# StepStick-Protector_v20.net
KiCad netlist of a schematic drawn in EAGLE
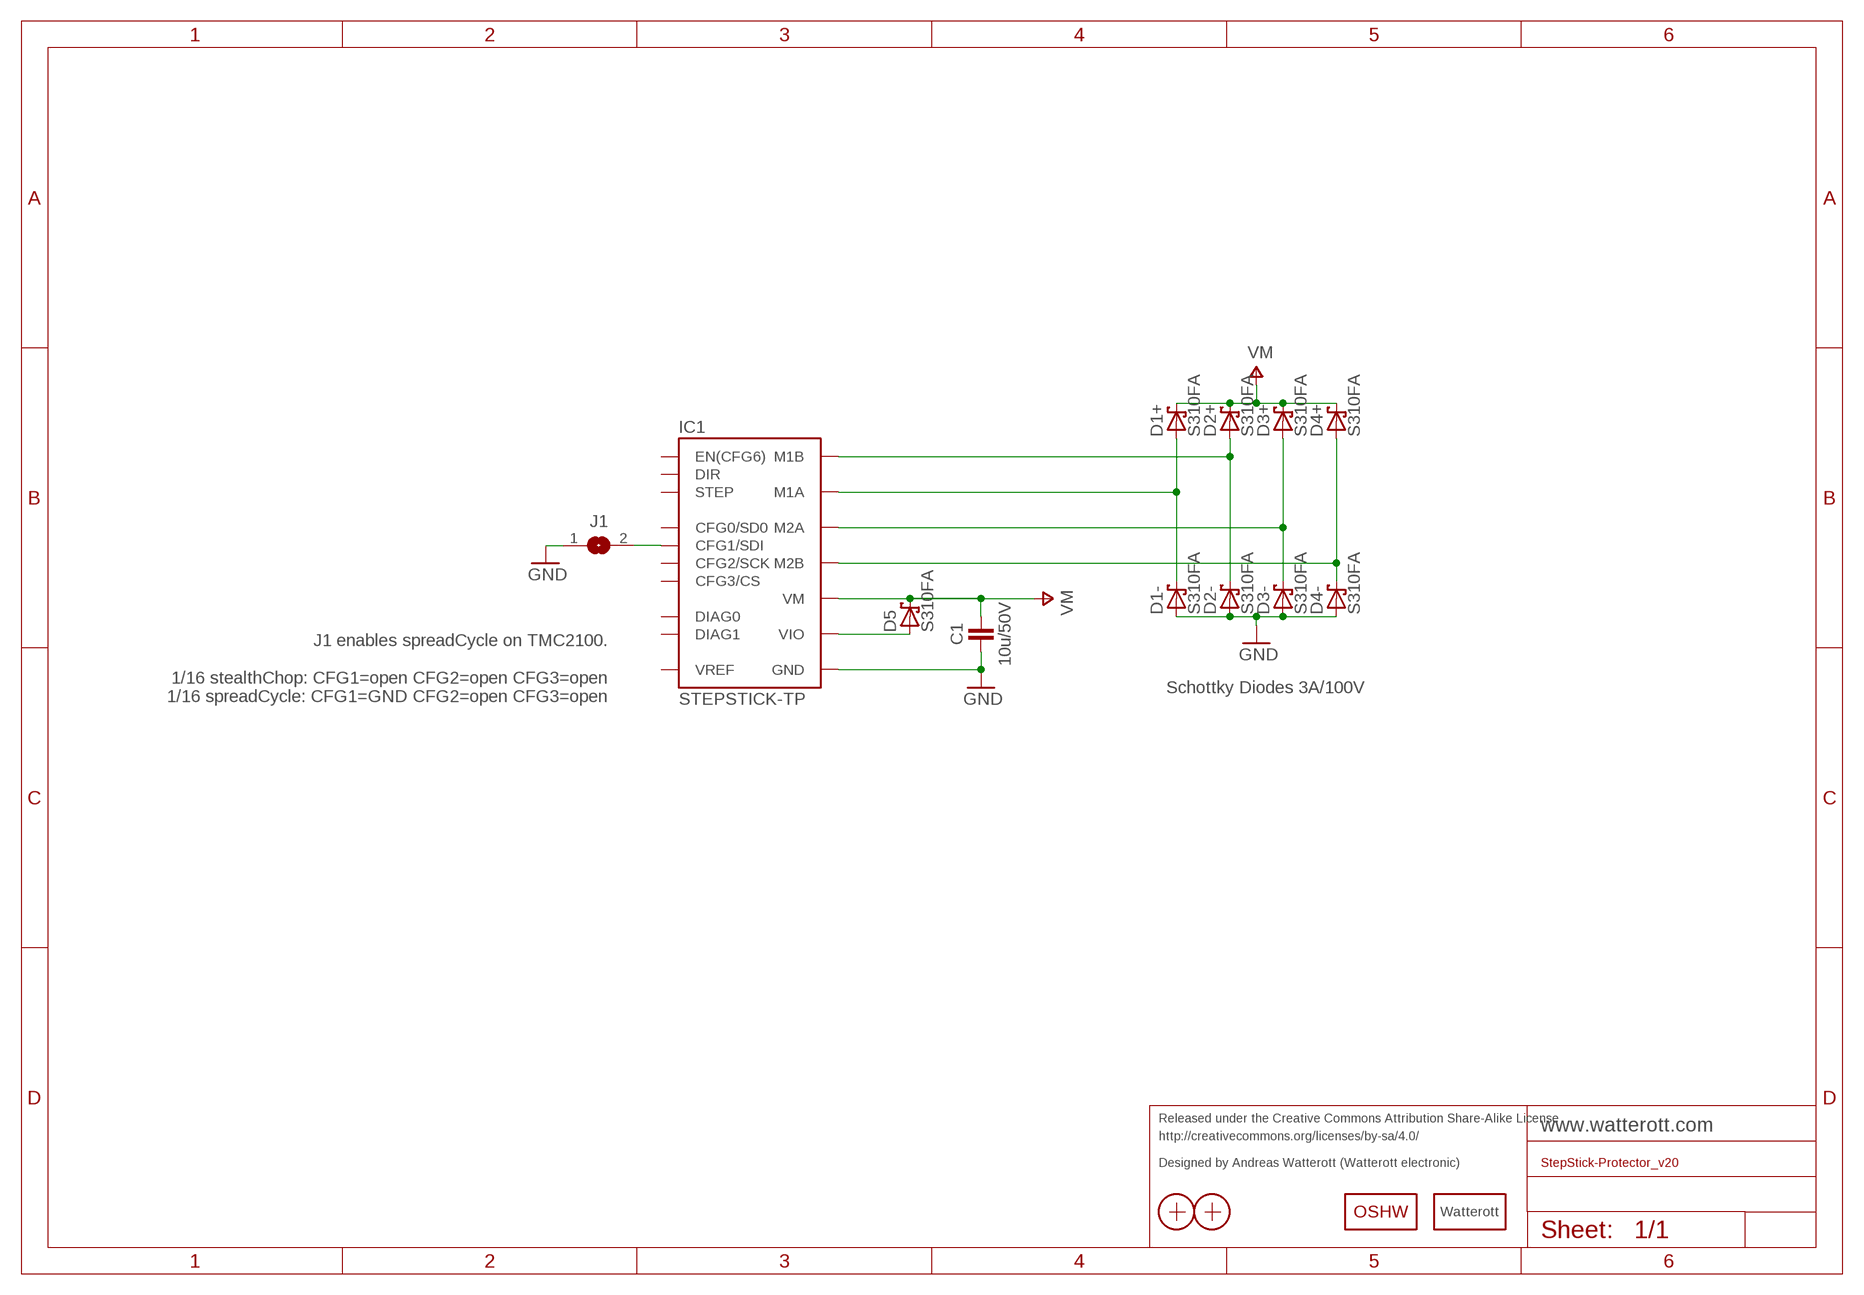
[diagram p0: schematic, sheet 1]

(export (version "E")
  (design (tool "Eeschema 10.0.6"))
  (components
    (comp (ref "C1")
      (value "10u/50V")
      (footprint "eagle-import:C1210")
      (libsource (lib "eagle-import") (part "CAPACITOR-1210"))
    )
    (comp (ref "D1+")
      (value "S310FA")
      (footprint "eagle-import:SOD123")
      (libsource (lib "eagle-import") (part "D_SCHOTTKY-SOD123"))
    )
    (comp (ref "D1-")
      (value "S310FA")
      (footprint "eagle-import:SOD123")
      (libsource (lib "eagle-import") (part "D_SCHOTTKY-SOD123"))
    )
    (comp (ref "D2+")
      (value "S310FA")
      (footprint "eagle-import:SOD123")
      (libsource (lib "eagle-import") (part "D_SCHOTTKY-SOD123"))
    )
    (comp (ref "D2-")
      (value "S310FA")
      (footprint "eagle-import:SOD123")
      (libsource (lib "eagle-import") (part "D_SCHOTTKY-SOD123"))
    )
    (comp (ref "D3+")
      (value "S310FA")
      (footprint "eagle-import:SOD123")
      (libsource (lib "eagle-import") (part "D_SCHOTTKY-SOD123"))
    )
    (comp (ref "D3-")
      (value "S310FA")
      (footprint "eagle-import:SOD123")
      (libsource (lib "eagle-import") (part "D_SCHOTTKY-SOD123"))
    )
    (comp (ref "D4+")
      (value "S310FA")
      (footprint "eagle-import:SOD123")
      (libsource (lib "eagle-import") (part "D_SCHOTTKY-SOD123"))
    )
    (comp (ref "D4-")
      (value "S310FA")
      (footprint "eagle-import:SOD123")
      (libsource (lib "eagle-import") (part "D_SCHOTTKY-SOD123"))
    )
    (comp (ref "D5")
      (value "S310FA")
      (footprint "eagle-import:SOD123")
      (libsource (lib "eagle-import") (part "D_SCHOTTKY-SOD123"))
    )
    (comp (ref "IC1")
      (value "STEPSTICK-TP")
      (footprint "eagle-import:STEPSTICK_TP")
      (libsource (lib "eagle-import") (part "STEPSTICK-TP"))
    )
    (comp (ref "J1")
      (value "JUMPER2-0603-NC")
      (footprint "eagle-import:JUMPER2-0603_NC")
      (libsource (lib "eagle-import") (part "JUMPER2-0603-NC"))
    )
    (comp (ref "LOGO1")
      (value "OSHW_LOGOX0070")
      (footprint "eagle-import:OSHW_6X70")
      (libsource (lib "eagle-import") (part "OSHW_LOGOX0070"))
    )
    (comp (ref "LOGO3")
      (value "LOGO_SPARK-2")
      (footprint "eagle-import:SPARK_2MM")
      (libsource (lib "eagle-import") (part "LOGO_SPARK-2"))
    )
    (comp (ref "X1")
      (value "PASSER")
      (footprint "eagle-import:PASSER")
      (libsource (lib "eagle-import") (part "PASSER"))
    )
    (comp (ref "X2")
      (value "PASSER")
      (footprint "eagle-import:PASSER")
      (libsource (lib "eagle-import") (part "PASSER"))
    )
  )
  (nets
    (net (code "1") (name "GND") (class "Default")
      (node (ref "C1") (pin "1") (pinfunction "1_1") (pintype "passive"))
      (node (ref "D1-") (pin "A") (pinfunction "A_A") (pintype "passive"))
      (node (ref "D2-") (pin "A") (pinfunction "A_A") (pintype "passive"))
      (node (ref "D3-") (pin "A") (pinfunction "A_A") (pintype "passive"))
      (node (ref "D4-") (pin "A") (pinfunction "A_A") (pintype "passive"))
      (node (ref "IC1") (pin "GND@1") (pinfunction "GND_GND@1") (pintype "power_in"))
      (node (ref "IC1") (pin "GND@2") (pinfunction "GND_GND@2") (pintype "power_in"))
      (node (ref "J1") (pin "1") (pinfunction "1_1") (pintype "passive"))
    )
    (net (code "2") (name "Net-(D1+-PadA)") (class "Default")
      (node (ref "D1+") (pin "A") (pinfunction "A_A") (pintype "passive"))
      (node (ref "D1-") (pin "C") (pinfunction "C_C") (pintype "passive"))
      (node (ref "IC1") (pin "M1A") (pinfunction "M1A_M1A") (pintype "output"))
    )
    (net (code "3") (name "Net-(D2+-PadA)") (class "Default")
      (node (ref "D2+") (pin "A") (pinfunction "A_A") (pintype "passive"))
      (node (ref "D2-") (pin "C") (pinfunction "C_C") (pintype "passive"))
      (node (ref "IC1") (pin "M1B") (pinfunction "M1B_M1B") (pintype "output"))
    )
    (net (code "4") (name "Net-(D3+-PadA)") (class "Default")
      (node (ref "D3+") (pin "A") (pinfunction "A_A") (pintype "passive"))
      (node (ref "D3-") (pin "C") (pinfunction "C_C") (pintype "passive"))
      (node (ref "IC1") (pin "M2A") (pinfunction "M2A_M2A") (pintype "output"))
    )
    (net (code "5") (name "Net-(D4+-PadA)") (class "Default")
      (node (ref "D4+") (pin "A") (pinfunction "A_A") (pintype "passive"))
      (node (ref "D4-") (pin "C") (pinfunction "C_C") (pintype "passive"))
      (node (ref "IC1") (pin "M2B") (pinfunction "M2B_M2B") (pintype "output"))
    )
    (net (code "6") (name "Net-(D5-PadA)") (class "Default")
      (node (ref "D5") (pin "A") (pinfunction "A_A") (pintype "passive"))
      (node (ref "IC1") (pin "VIO") (pinfunction "VIO_VIO") (pintype "power_in"))
    )
    (net (code "7") (name "Net-(IC1-CFG1{slash}SDI)") (class "Default")
      (node (ref "IC1") (pin "CFG1") (pinfunction "CFG1/SDI_CFG1") (pintype "bidirectional"))
      (node (ref "J1") (pin "2") (pinfunction "2_2") (pintype "passive"))
    )
    (net (code "8") (name "VM") (class "Default")
      (node (ref "C1") (pin "2") (pinfunction "2_2") (pintype "passive"))
      (node (ref "D1+") (pin "C") (pinfunction "C_C") (pintype "passive"))
      (node (ref "D2+") (pin "C") (pinfunction "C_C") (pintype "passive"))
      (node (ref "D3+") (pin "C") (pinfunction "C_C") (pintype "passive"))
      (node (ref "D4+") (pin "C") (pinfunction "C_C") (pintype "passive"))
      (node (ref "D5") (pin "C") (pinfunction "C_C") (pintype "passive"))
      (node (ref "IC1") (pin "VM") (pinfunction "VM_VM") (pintype "power_in"))
    )
    (net (code "9") (name "unconnected-(IC1-CFG0{slash}SD0-PadNC{slash}CFG0)") (class "Default")
      (node (ref "IC1") (pin "NC/CFG0") (pinfunction "CFG0/SD0_NC/CFG0") (pintype "bidirectional"))
    )
    (net (code "10") (name "unconnected-(IC1-CFG2{slash}SCK-PadCFG2)") (class "Default")
      (node (ref "IC1") (pin "CFG2") (pinfunction "CFG2/SCK_CFG2") (pintype "bidirectional"))
    )
    (net (code "11") (name "unconnected-(IC1-CFG3{slash}CS-PadCFG3)") (class "Default")
      (node (ref "IC1") (pin "CFG3") (pinfunction "CFG3/CS_CFG3") (pintype "bidirectional"))
    )
    (net (code "12") (name "unconnected-(IC1-EN(CFG6)-PadEN)") (class "Default")
      (node (ref "IC1") (pin "EN") (pinfunction "EN(CFG6)_EN") (pintype "bidirectional"))
    )
    (net (code "13") (name "unconnected-(IC1-PadDIAG0)") (class "Default")
      (node (ref "IC1") (pin "DIAG0") (pinfunction "DIAG0_DIAG0") (pintype "bidirectional"))
    )
    (net (code "14") (name "unconnected-(IC1-PadDIAG1)") (class "Default")
      (node (ref "IC1") (pin "DIAG1") (pinfunction "DIAG1_DIAG1") (pintype "bidirectional"))
    )
    (net (code "15") (name "unconnected-(IC1-PadDIR)") (class "Default")
      (node (ref "IC1") (pin "DIR") (pinfunction "DIR_DIR") (pintype "bidirectional"))
    )
    (net (code "16") (name "unconnected-(IC1-PadSTEP)") (class "Default")
      (node (ref "IC1") (pin "STEP") (pinfunction "STEP_STEP") (pintype "bidirectional"))
    )
    (net (code "17") (name "unconnected-(IC1-PadVREF)") (class "Default")
      (node (ref "IC1") (pin "VREF") (pinfunction "VREF_VREF") (pintype "passive"))
    )
  )
)
